# pm2018.net
KiCad netlist of a schematic drawn in EAGLE
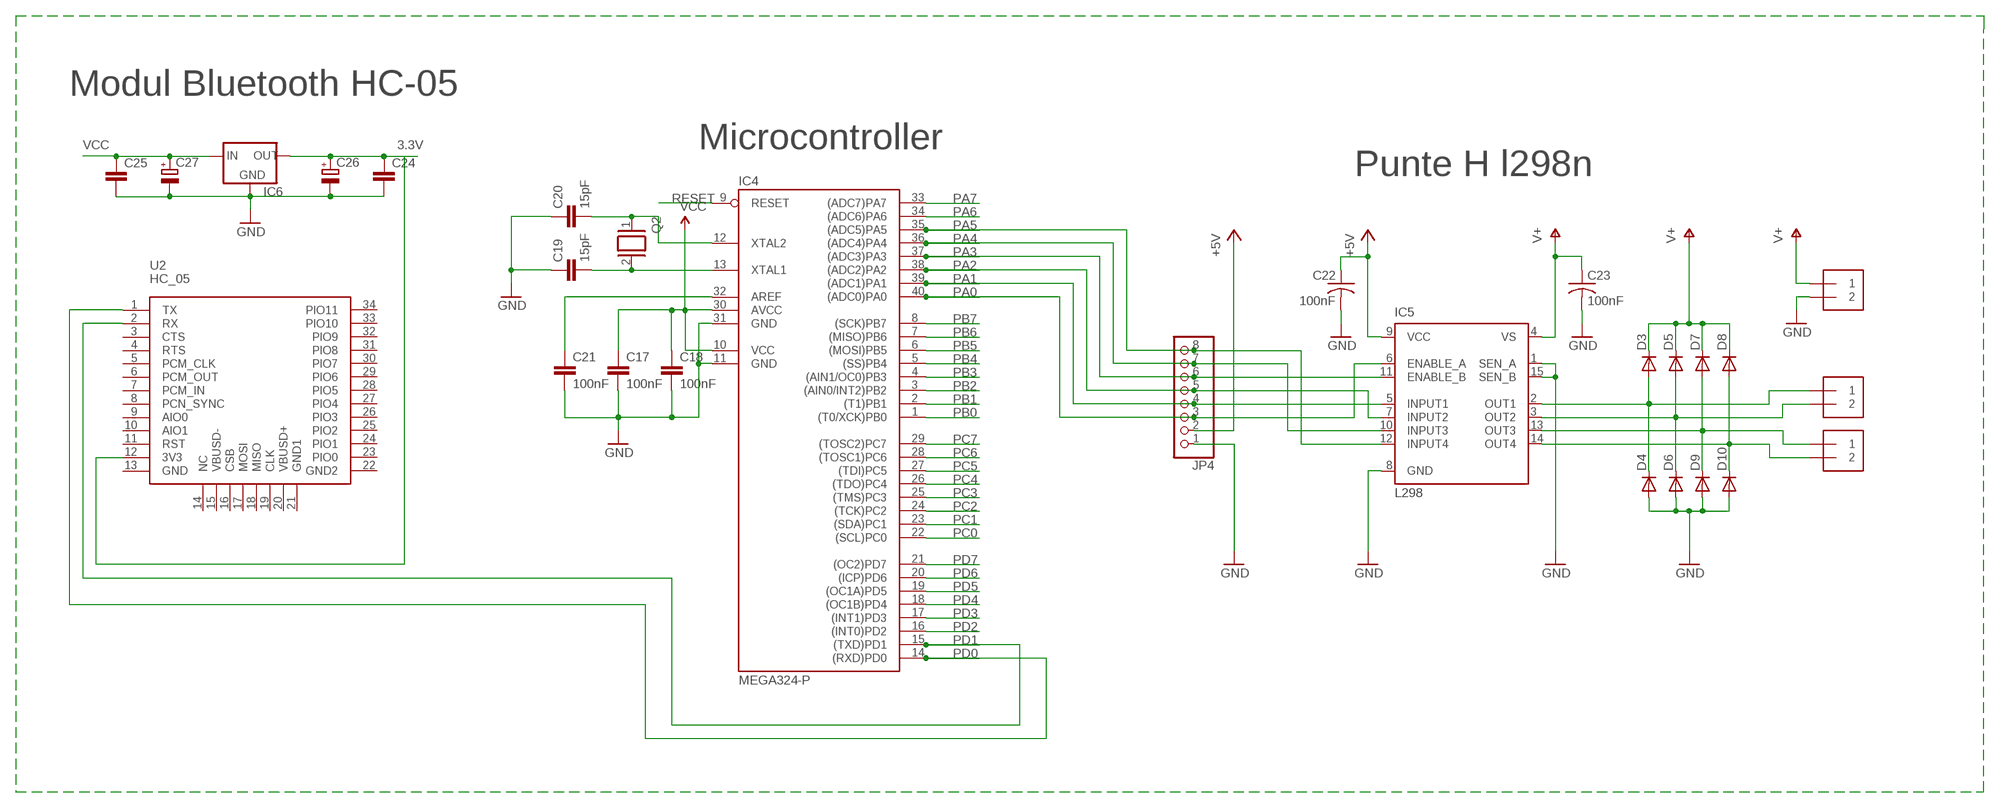
[diagram p0: schematic, sheet 1]

(export (version "E")
  (design (tool "Eeschema 10.0.6"))
  (components
    (comp (ref "C17")
      (value "100nF")
      (footprint "eagle-import:C025-025X050")
      (libsource (lib "eagle-import") (part "C-EUC_PM"))
    )
    (comp (ref "C18")
      (value "100nF")
      (footprint "eagle-import:C025-025X050")
      (libsource (lib "eagle-import") (part "C-EUC_PM"))
    )
    (comp (ref "C19")
      (value "15pF")
      (footprint "eagle-import:C025-025X050")
      (libsource (lib "eagle-import") (part "C-EUC_PM"))
    )
    (comp (ref "C20")
      (value "15pF")
      (footprint "eagle-import:C025-025X050")
      (libsource (lib "eagle-import") (part "C-EUC_PM"))
    )
    (comp (ref "C21")
      (value "100nF")
      (footprint "eagle-import:C025-025X050")
      (libsource (lib "eagle-import") (part "C-EUC_PM"))
    )
    (comp (ref "C22")
      (value "100nF")
      (footprint "eagle-import:C050-024X044")
      (libsource (lib "eagle-import") (part "C-US050-024X044"))
    )
    (comp (ref "C23")
      (value "100nF")
      (footprint "eagle-import:C050-024X044")
      (libsource (lib "eagle-import") (part "C-US050-024X044"))
    )
    (comp (ref "C24")
      (value "C2,5-3")
      (footprint "eagle-import:C2.5-3")
      (libsource (lib "eagle-import") (part "C2,5-3"))
    )
    (comp (ref "C25")
      (value "C2,5-3")
      (footprint "eagle-import:C2.5-3")
      (libsource (lib "eagle-import") (part "C2,5-3"))
    )
    (comp (ref "C26")
      (value "CPOL-EUE5-5")
      (footprint "eagle-import:E5-5")
      (libsource (lib "eagle-import") (part "CPOL-EUE5-5"))
    )
    (comp (ref "C27")
      (value "CPOL-EUE5-5")
      (footprint "eagle-import:E5-5")
      (libsource (lib "eagle-import") (part "CPOL-EUE5-5"))
    )
    (comp (ref "D3")
      (value "DIODE-D-5")
      (footprint "eagle-import:D-5")
      (libsource (lib "eagle-import") (part "DIODE-D-5"))
    )
    (comp (ref "D4")
      (value "DIODE-D-5")
      (footprint "eagle-import:D-5")
      (libsource (lib "eagle-import") (part "DIODE-D-5"))
    )
    (comp (ref "D5")
      (value "DIODE-D-5")
      (footprint "eagle-import:D-5")
      (libsource (lib "eagle-import") (part "DIODE-D-5"))
    )
    (comp (ref "D6")
      (value "DIODE-D-5")
      (footprint "eagle-import:D-5")
      (libsource (lib "eagle-import") (part "DIODE-D-5"))
    )
    (comp (ref "D7")
      (value "DIODE-D-5")
      (footprint "eagle-import:D-5")
      (libsource (lib "eagle-import") (part "DIODE-D-5"))
    )
    (comp (ref "D8")
      (value "DIODE-D-5")
      (footprint "eagle-import:D-5")
      (libsource (lib "eagle-import") (part "DIODE-D-5"))
    )
    (comp (ref "D9")
      (value "DIODE-D-5")
      (footprint "eagle-import:D-5")
      (libsource (lib "eagle-import") (part "DIODE-D-5"))
    )
    (comp (ref "D10")
      (value "DIODE-D-5")
      (footprint "eagle-import:D-5")
      (libsource (lib "eagle-import") (part "DIODE-D-5"))
    )
    (comp (ref "IC4")
      (value "MEGA324-P")
      (footprint "eagle-import:DIL40")
      (fields (field (name "MPN") "ATMEGA16-16PU"))
      (libsource (lib "eagle-import") (part "MEGA16-P"))
    )
    (comp (ref "IC5")
      (value "L298")
      (footprint "eagle-import:MULTIWATT-15")
      (fields (field (name "MPN") "L298N"))
      (libsource (lib "eagle-import") (part "L298"))
    )
    (comp (ref "IC6")
      (value "MCP1700INLINE")
      (footprint "eagle-import:TO92-INLINE")
      (libsource (lib "eagle-import") (part "MCP1700INLINE"))
    )
    (comp (ref "J4")
      (value "1X2-3.5MM")
      (footprint "eagle-import:1X2-3.5MM")
      (libsource (lib "eagle-import") (part "1X2-3.5MM"))
    )
    (comp (ref "J5")
      (value "1X2-3.5MM")
      (footprint "eagle-import:1X2-3.5MM")
      (libsource (lib "eagle-import") (part "1X2-3.5MM"))
    )
    (comp (ref "J6")
      (value "1X2-3.5MM")
      (footprint "eagle-import:1X2-3.5MM")
      (libsource (lib "eagle-import") (part "1X2-3.5MM"))
    )
    (comp (ref "JP4")
      (value "PINHD-1X8")
      (footprint "eagle-import:1X08")
      (libsource (lib "eagle-import") (part "PINHD-1X8"))
    )
    (comp (ref "Q2")
      (value "XTAL/S")
      (footprint "eagle-import:QS")
      (libsource (lib "eagle-import") (part "XTAL/S"))
    )
    (comp (ref "U2")
      (value "HC_05")
      (footprint "eagle-import:BLUETOOTH_SMD")
      (libsource (lib "eagle-import") (part "HC_05"))
    )
  )
  (nets
    (net (code "1") (name "+5V") (class "Default")
      (node (ref "C22") (pin "1") (pinfunction "1_1") (pintype "passive"))
      (node (ref "IC5") (pin "9") (pinfunction "VCC_9") (pintype "power_in"))
      (node (ref "JP4") (pin "2") (pinfunction "2_2") (pintype "passive"))
    )
    (net (code "2") (name "/3.3V") (class "Default")
      (node (ref "C24") (pin "1") (pinfunction "1_1") (pintype "passive"))
      (node (ref "C26") (pin "+") (pinfunction "+_+") (pintype "passive"))
      (node (ref "IC6") (pin "3") (pinfunction "OUT_3") (pintype "passive"))
      (node (ref "U2") (pin "12") (pinfunction "3V3_12") (pintype "bidirectional"))
    )
    (net (code "3") (name "/PA0") (class "Default")
      (node (ref "IC4") (pin "40") (pinfunction "(ADC0)PA0_40") (pintype "bidirectional"))
      (node (ref "IC5") (pin "6") (pinfunction "ENABLE_A_6") (pintype "input"))
      (node (ref "JP4") (pin "3") (pinfunction "3_3") (pintype "passive"))
    )
    (net (code "4") (name "/PA1") (class "Default")
      (node (ref "IC4") (pin "39") (pinfunction "(ADC1)PA1_39") (pintype "bidirectional"))
      (node (ref "IC5") (pin "5") (pinfunction "INPUT1_5") (pintype "input"))
      (node (ref "JP4") (pin "4") (pinfunction "4_4") (pintype "passive"))
    )
    (net (code "5") (name "/PA2") (class "Default")
      (node (ref "IC4") (pin "38") (pinfunction "(ADC2)PA2_38") (pintype "bidirectional"))
      (node (ref "IC5") (pin "7") (pinfunction "INPUT2_7") (pintype "input"))
      (node (ref "JP4") (pin "5") (pinfunction "5_5") (pintype "passive"))
    )
    (net (code "6") (name "/PA3") (class "Default")
      (node (ref "IC4") (pin "37") (pinfunction "(ADC3)PA3_37") (pintype "bidirectional"))
      (node (ref "IC5") (pin "11") (pinfunction "ENABLE_B_11") (pintype "input"))
      (node (ref "JP4") (pin "6") (pinfunction "6_6") (pintype "passive"))
    )
    (net (code "7") (name "/PA4") (class "Default")
      (node (ref "IC4") (pin "36") (pinfunction "(ADC4)PA4_36") (pintype "bidirectional"))
      (node (ref "IC5") (pin "10") (pinfunction "INPUT3_10") (pintype "input"))
      (node (ref "JP4") (pin "7") (pinfunction "7_7") (pintype "passive"))
    )
    (net (code "8") (name "/PA5") (class "Default")
      (node (ref "IC4") (pin "35") (pinfunction "(ADC5)PA5_35") (pintype "bidirectional"))
      (node (ref "IC5") (pin "12") (pinfunction "INPUT4_12") (pintype "input"))
      (node (ref "JP4") (pin "8") (pinfunction "8_8") (pintype "passive"))
    )
    (net (code "9") (name "/PA6") (class "Default")
      (node (ref "IC4") (pin "34") (pinfunction "(ADC6)PA6_34") (pintype "bidirectional"))
    )
    (net (code "10") (name "/PA7") (class "Default")
      (node (ref "IC4") (pin "33") (pinfunction "(ADC7)PA7_33") (pintype "bidirectional"))
    )
    (net (code "11") (name "/PB0") (class "Default")
      (node (ref "IC4") (pin "1") (pinfunction "(T0/XCK)PB0_1") (pintype "bidirectional"))
    )
    (net (code "12") (name "/PB1") (class "Default")
      (node (ref "IC4") (pin "2") (pinfunction "(T1)PB1_2") (pintype "bidirectional"))
    )
    (net (code "13") (name "/PB2") (class "Default")
      (node (ref "IC4") (pin "3") (pinfunction "(AIN0/INT2)PB2_3") (pintype "bidirectional"))
    )
    (net (code "14") (name "/PB3") (class "Default")
      (node (ref "IC4") (pin "4") (pinfunction "(AIN1/OC0)PB3_4") (pintype "bidirectional"))
    )
    (net (code "15") (name "/PB4") (class "Default")
      (node (ref "IC4") (pin "5") (pinfunction "(SS)PB4_5") (pintype "bidirectional"))
    )
    (net (code "16") (name "/PB5") (class "Default")
      (node (ref "IC4") (pin "6") (pinfunction "(MOSI)PB5_6") (pintype "bidirectional"))
    )
    (net (code "17") (name "/PB6") (class "Default")
      (node (ref "IC4") (pin "7") (pinfunction "(MISO)PB6_7") (pintype "bidirectional"))
    )
    (net (code "18") (name "/PB7") (class "Default")
      (node (ref "IC4") (pin "8") (pinfunction "(SCK)PB7_8") (pintype "bidirectional"))
    )
    (net (code "19") (name "/PC0") (class "Default")
      (node (ref "IC4") (pin "22") (pinfunction "(SCL)PC0_22") (pintype "bidirectional"))
    )
    (net (code "20") (name "/PC1") (class "Default")
      (node (ref "IC4") (pin "23") (pinfunction "(SDA)PC1_23") (pintype "bidirectional"))
    )
    (net (code "21") (name "/PC2") (class "Default")
      (node (ref "IC4") (pin "24") (pinfunction "(TCK)PC2_24") (pintype "bidirectional"))
    )
    (net (code "22") (name "/PC3") (class "Default")
      (node (ref "IC4") (pin "25") (pinfunction "(TMS)PC3_25") (pintype "bidirectional"))
    )
    (net (code "23") (name "/PC4") (class "Default")
      (node (ref "IC4") (pin "26") (pinfunction "(TDO)PC4_26") (pintype "bidirectional"))
    )
    (net (code "24") (name "/PC5") (class "Default")
      (node (ref "IC4") (pin "27") (pinfunction "(TDI)PC5_27") (pintype "bidirectional"))
    )
    (net (code "25") (name "/PC6") (class "Default")
      (node (ref "IC4") (pin "28") (pinfunction "(TOSC1)PC6_28") (pintype "bidirectional"))
    )
    (net (code "26") (name "/PC7") (class "Default")
      (node (ref "IC4") (pin "29") (pinfunction "(TOSC2)PC7_29") (pintype "bidirectional"))
    )
    (net (code "27") (name "/PD0") (class "Default")
      (node (ref "IC4") (pin "14") (pinfunction "(RXD)PD0_14") (pintype "bidirectional"))
      (node (ref "U2") (pin "1") (pinfunction "TX_1") (pintype "bidirectional"))
    )
    (net (code "28") (name "/PD1") (class "Default")
      (node (ref "IC4") (pin "15") (pinfunction "(TXD)PD1_15") (pintype "bidirectional"))
      (node (ref "U2") (pin "2") (pinfunction "RX_2") (pintype "bidirectional"))
    )
    (net (code "29") (name "/PD2") (class "Default")
      (node (ref "IC4") (pin "16") (pinfunction "(INT0)PD2_16") (pintype "bidirectional"))
    )
    (net (code "30") (name "/PD3") (class "Default")
      (node (ref "IC4") (pin "17") (pinfunction "(INT1)PD3_17") (pintype "bidirectional"))
    )
    (net (code "31") (name "/PD4") (class "Default")
      (node (ref "IC4") (pin "18") (pinfunction "(OC1B)PD4_18") (pintype "bidirectional"))
    )
    (net (code "32") (name "/PD5") (class "Default")
      (node (ref "IC4") (pin "19") (pinfunction "(OC1A)PD5_19") (pintype "bidirectional"))
    )
    (net (code "33") (name "/PD6") (class "Default")
      (node (ref "IC4") (pin "20") (pinfunction "(ICP)PD6_20") (pintype "bidirectional"))
    )
    (net (code "34") (name "/PD7") (class "Default")
      (node (ref "IC4") (pin "21") (pinfunction "(OC2)PD7_21") (pintype "bidirectional"))
    )
    (net (code "35") (name "/RESET") (class "Default")
      (node (ref "IC4") (pin "9") (pinfunction "RESET_9") (pintype "input"))
    )
    (net (code "36") (name "GND") (class "Default")
      (node (ref "C17") (pin "2") (pinfunction "2_2") (pintype "passive"))
      (node (ref "C18") (pin "2") (pinfunction "2_2") (pintype "passive"))
      (node (ref "C19") (pin "1") (pinfunction "1_1") (pintype "passive"))
      (node (ref "C20") (pin "1") (pinfunction "1_1") (pintype "passive"))
      (node (ref "C21") (pin "2") (pinfunction "2_2") (pintype "passive"))
      (node (ref "C22") (pin "2") (pinfunction "2_2") (pintype "passive"))
      (node (ref "C23") (pin "2") (pinfunction "2_2") (pintype "passive"))
      (node (ref "C24") (pin "2") (pinfunction "2_2") (pintype "passive"))
      (node (ref "C25") (pin "2") (pinfunction "2_2") (pintype "passive"))
      (node (ref "C26") (pin "-") (pinfunction "-_-") (pintype "passive"))
      (node (ref "C27") (pin "-") (pinfunction "-_-") (pintype "passive"))
      (node (ref "D10") (pin "A") (pinfunction "A_A") (pintype "passive"))
      (node (ref "D4") (pin "A") (pinfunction "A_A") (pintype "passive"))
      (node (ref "D6") (pin "A") (pinfunction "A_A") (pintype "passive"))
      (node (ref "D9") (pin "A") (pinfunction "A_A") (pintype "passive"))
      (node (ref "IC4") (pin "11") (pinfunction "GND_11") (pintype "power_in"))
      (node (ref "IC4") (pin "31") (pinfunction "GND_31") (pintype "power_in"))
      (node (ref "IC5") (pin "1") (pinfunction "SEN_A_1") (pintype "input"))
      (node (ref "IC5") (pin "15") (pinfunction "SEN_B_15") (pintype "input"))
      (node (ref "IC5") (pin "8") (pinfunction "GND_8") (pintype "power_in"))
      (node (ref "IC6") (pin "1") (pinfunction "GND_1") (pintype "input"))
      (node (ref "J4") (pin "2") (pinfunction "2_2") (pintype "passive"))
      (node (ref "JP4") (pin "1") (pinfunction "1_1") (pintype "passive"))
    )
    (net (code "37") (name "Net-(IC4-AREF)") (class "Default")
      (node (ref "C21") (pin "1") (pinfunction "1_1") (pintype "passive"))
      (node (ref "IC4") (pin "32") (pinfunction "AREF_32") (pintype "passive"))
    )
    (net (code "38") (name "Net-(IC4-XTAL1)") (class "Default")
      (node (ref "C19") (pin "2") (pinfunction "2_2") (pintype "passive"))
      (node (ref "IC4") (pin "13") (pinfunction "XTAL1_13") (pintype "bidirectional"))
      (node (ref "Q2") (pin "2") (pinfunction "2_2") (pintype "passive"))
    )
    (net (code "39") (name "Net-(IC4-XTAL2)") (class "Default")
      (node (ref "C20") (pin "2") (pinfunction "2_2") (pintype "passive"))
      (node (ref "IC4") (pin "12") (pinfunction "XTAL2_12") (pintype "bidirectional"))
      (node (ref "Q2") (pin "1") (pinfunction "1_1") (pintype "passive"))
    )
    (net (code "40") (name "Net-(IC5-OUT1)") (class "Default")
      (node (ref "D3") (pin "A") (pinfunction "A_A") (pintype "passive"))
      (node (ref "D4") (pin "C") (pinfunction "C_C") (pintype "passive"))
      (node (ref "IC5") (pin "2") (pinfunction "OUT1_2") (pintype "output"))
      (node (ref "J5") (pin "1") (pinfunction "1_1") (pintype "passive"))
    )
    (net (code "41") (name "Net-(IC5-OUT2)") (class "Default")
      (node (ref "D5") (pin "A") (pinfunction "A_A") (pintype "passive"))
      (node (ref "D6") (pin "C") (pinfunction "C_C") (pintype "passive"))
      (node (ref "IC5") (pin "3") (pinfunction "OUT2_3") (pintype "output"))
      (node (ref "J5") (pin "2") (pinfunction "2_2") (pintype "passive"))
    )
    (net (code "42") (name "Net-(IC5-OUT3)") (class "Default")
      (node (ref "D7") (pin "A") (pinfunction "A_A") (pintype "passive"))
      (node (ref "D9") (pin "C") (pinfunction "C_C") (pintype "passive"))
      (node (ref "IC5") (pin "13") (pinfunction "OUT3_13") (pintype "output"))
      (node (ref "J6") (pin "1") (pinfunction "1_1") (pintype "passive"))
    )
    (net (code "43") (name "Net-(IC5-OUT4)") (class "Default")
      (node (ref "D10") (pin "C") (pinfunction "C_C") (pintype "passive"))
      (node (ref "D8") (pin "A") (pinfunction "A_A") (pintype "passive"))
      (node (ref "IC5") (pin "14") (pinfunction "OUT4_14") (pintype "output"))
      (node (ref "J6") (pin "2") (pinfunction "2_2") (pintype "passive"))
    )
    (net (code "44") (name "V+") (class "Default")
      (node (ref "C23") (pin "1") (pinfunction "1_1") (pintype "passive"))
      (node (ref "D3") (pin "C") (pinfunction "C_C") (pintype "passive"))
      (node (ref "D5") (pin "C") (pinfunction "C_C") (pintype "passive"))
      (node (ref "D7") (pin "C") (pinfunction "C_C") (pintype "passive"))
      (node (ref "D8") (pin "C") (pinfunction "C_C") (pintype "passive"))
      (node (ref "IC5") (pin "4") (pinfunction "VS_4") (pintype "power_in"))
      (node (ref "J4") (pin "1") (pinfunction "1_1") (pintype "passive"))
    )
    (net (code "45") (name "VCC") (class "Default")
      (node (ref "C17") (pin "1") (pinfunction "1_1") (pintype "passive"))
      (node (ref "C18") (pin "1") (pinfunction "1_1") (pintype "passive"))
      (node (ref "C25") (pin "1") (pinfunction "1_1") (pintype "passive"))
      (node (ref "C27") (pin "+") (pinfunction "+_+") (pintype "passive"))
      (node (ref "IC4") (pin "10") (pinfunction "VCC_10") (pintype "power_in"))
      (node (ref "IC4") (pin "30") (pinfunction "AVCC_30") (pintype "power_in"))
      (node (ref "IC6") (pin "2") (pinfunction "IN_2") (pintype "input"))
    )
    (net (code "46") (name "unconnected-(U2-AIO0-Pad9)") (class "Default")
      (node (ref "U2") (pin "9") (pinfunction "AIO0_9") (pintype "bidirectional"))
    )
    (net (code "47") (name "unconnected-(U2-AIO1-Pad10)") (class "Default")
      (node (ref "U2") (pin "10") (pinfunction "AIO1_10") (pintype "bidirectional"))
    )
    (net (code "48") (name "unconnected-(U2-CLK-Pad19)") (class "Default")
      (node (ref "U2") (pin "19") (pinfunction "CLK_19") (pintype "bidirectional"))
    )
    (net (code "49") (name "unconnected-(U2-CSB-Pad16)") (class "Default")
      (node (ref "U2") (pin "16") (pinfunction "CSB_16") (pintype "bidirectional"))
    )
    (net (code "50") (name "unconnected-(U2-CTS-Pad3)") (class "Default")
      (node (ref "U2") (pin "3") (pinfunction "CTS_3") (pintype "bidirectional"))
    )
    (net (code "51") (name "unconnected-(U2-GND-Pad13)") (class "Default")
      (node (ref "U2") (pin "13") (pinfunction "GND_13") (pintype "bidirectional"))
    )
    (net (code "52") (name "unconnected-(U2-GND1-Pad21)") (class "Default")
      (node (ref "U2") (pin "21") (pinfunction "GND1_21") (pintype "bidirectional"))
    )
    (net (code "53") (name "unconnected-(U2-GND2-Pad22)") (class "Default")
      (node (ref "U2") (pin "22") (pinfunction "GND2_22") (pintype "bidirectional"))
    )
    (net (code "54") (name "unconnected-(U2-MISO-Pad18)") (class "Default")
      (node (ref "U2") (pin "18") (pinfunction "MISO_18") (pintype "bidirectional"))
    )
    (net (code "55") (name "unconnected-(U2-MOSI-Pad17)") (class "Default")
      (node (ref "U2") (pin "17") (pinfunction "MOSI_17") (pintype "bidirectional"))
    )
    (net (code "56") (name "unconnected-(U2-NC-Pad14)") (class "Default")
      (node (ref "U2") (pin "14") (pinfunction "NC_14") (pintype "bidirectional"))
    )
    (net (code "57") (name "unconnected-(U2-PCM_CLK-Pad5)") (class "Default")
      (node (ref "U2") (pin "5") (pinfunction "PCM_CLK_5") (pintype "bidirectional"))
    )
    (net (code "58") (name "unconnected-(U2-PCM_IN-Pad7)") (class "Default")
      (node (ref "U2") (pin "7") (pinfunction "PCM_IN_7") (pintype "bidirectional"))
    )
    (net (code "59") (name "unconnected-(U2-PCM_OUT-Pad6)") (class "Default")
      (node (ref "U2") (pin "6") (pinfunction "PCM_OUT_6") (pintype "bidirectional"))
    )
    (net (code "60") (name "unconnected-(U2-PCN_SYNC-Pad8)") (class "Default")
      (node (ref "U2") (pin "8") (pinfunction "PCN_SYNC_8") (pintype "bidirectional"))
    )
    (net (code "61") (name "unconnected-(U2-PIO0-Pad23)") (class "Default")
      (node (ref "U2") (pin "23") (pinfunction "PIO0_23") (pintype "bidirectional"))
    )
    (net (code "62") (name "unconnected-(U2-PIO1-Pad24)") (class "Default")
      (node (ref "U2") (pin "24") (pinfunction "PIO1_24") (pintype "bidirectional"))
    )
    (net (code "63") (name "unconnected-(U2-PIO2-Pad25)") (class "Default")
      (node (ref "U2") (pin "25") (pinfunction "PIO2_25") (pintype "bidirectional"))
    )
    (net (code "64") (name "unconnected-(U2-PIO3-Pad26)") (class "Default")
      (node (ref "U2") (pin "26") (pinfunction "PIO3_26") (pintype "bidirectional"))
    )
    (net (code "65") (name "unconnected-(U2-PIO4-Pad27)") (class "Default")
      (node (ref "U2") (pin "27") (pinfunction "PIO4_27") (pintype "bidirectional"))
    )
    (net (code "66") (name "unconnected-(U2-PIO5-Pad28)") (class "Default")
      (node (ref "U2") (pin "28") (pinfunction "PIO5_28") (pintype "bidirectional"))
    )
    (net (code "67") (name "unconnected-(U2-PIO6-Pad29)") (class "Default")
      (node (ref "U2") (pin "29") (pinfunction "PIO6_29") (pintype "bidirectional"))
    )
    (net (code "68") (name "unconnected-(U2-PIO7-Pad30)") (class "Default")
      (node (ref "U2") (pin "30") (pinfunction "PIO7_30") (pintype "bidirectional"))
    )
    (net (code "69") (name "unconnected-(U2-PIO8-Pad31)") (class "Default")
      (node (ref "U2") (pin "31") (pinfunction "PIO8_31") (pintype "bidirectional"))
    )
    (net (code "70") (name "unconnected-(U2-PIO9-Pad32)") (class "Default")
      (node (ref "U2") (pin "32") (pinfunction "PIO9_32") (pintype "bidirectional"))
    )
    (net (code "71") (name "unconnected-(U2-PIO10-Pad33)") (class "Default")
      (node (ref "U2") (pin "33") (pinfunction "PIO10_33") (pintype "bidirectional"))
    )
    (net (code "72") (name "unconnected-(U2-PIO11-Pad34)") (class "Default")
      (node (ref "U2") (pin "34") (pinfunction "PIO11_34") (pintype "bidirectional"))
    )
    (net (code "73") (name "unconnected-(U2-RST-Pad11)") (class "Default")
      (node (ref "U2") (pin "11") (pinfunction "RST_11") (pintype "bidirectional"))
    )
    (net (code "74") (name "unconnected-(U2-RTS-Pad4)") (class "Default")
      (node (ref "U2") (pin "4") (pinfunction "RTS_4") (pintype "bidirectional"))
    )
    (net (code "75") (name "unconnected-(U2-VBUSD+-Pad20)") (class "Default")
      (node (ref "U2") (pin "20") (pinfunction "VBUSD+_20") (pintype "bidirectional"))
    )
    (net (code "76") (name "unconnected-(U2-VBUSD--Pad15)") (class "Default")
      (node (ref "U2") (pin "15") (pinfunction "VBUSD-_15") (pintype "bidirectional"))
    )
  )
)
